# sensors.net
KiCad netlist of a schematic drawn in Altium Designer
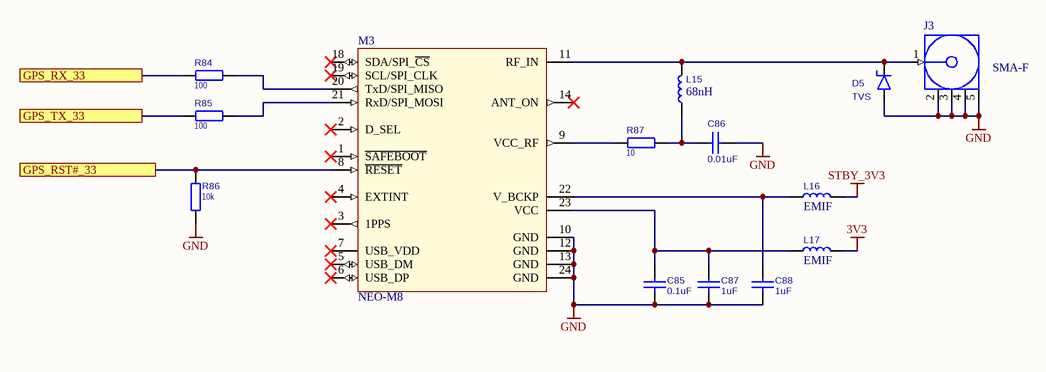
[diagram p0: sensors.SchDoc]

(export (version "E")
  (design (tool "Eeschema 10.0.6"))
  (components
    (comp (ref "C85")
      (value "0.1uF")
      (footprint "Capacitors:C0603")
      (description "CAP_NPOL")
      (fields (field (name "Comment") "C1608X7R1H104K080AA"))
      (libsource (lib "capacitors") (part "CAP_NPOL"))
    )
    (comp (ref "C86")
      (value "0.01uF")
      (footprint "Capacitors:C0603")
      (description "CAP_NPOL")
      (fields (field (name "Comment") "CL10B103KB8NNNC"))
      (libsource (lib "capacitors") (part "CAP_NPOL"))
    )
    (comp (ref "C87")
      (value "1uF")
      (footprint "Capacitors:C0603")
      (description "CAP_NPOL")
      (fields (field (name "Comment") "GRM188R61H105KAALD"))
      (libsource (lib "capacitors") (part "CAP_NPOL"))
    )
    (comp (ref "C88")
      (value "1uF")
      (footprint "Capacitors:C0603")
      (description "CAP_NPOL")
      (fields (field (name "Comment") "GRM188R61H105KAALD"))
      (libsource (lib "capacitors") (part "CAP_NPOL"))
    )
    (comp (ref "D5")
      (value "TVS")
      (footprint "SOD-323")
      (description "TVS Diode")
      (fields (field (name "Comment") "CDSOD323-T05LC"))
      (libsource (lib "diodes") (part "ZENNER_1"))
    )
    (comp (ref "J3")
      (value "SMA-F")
      (footprint "MCX5.08-H5")
      (fields
        (field (name "Comment") "CON SMA-F S-037-TGG R/A PCB")
        (field (name "PUBLISHER") "Altium Limited")
      )
      (libsource (lib "Miscellaneous Connectors") (part "COAX-F"))
    )
    (comp (ref "L15")
      (value "68nH")
      (footprint "IND0603")
      (description "IND_WO_IRON")
      (fields (field (name "Comment") "CLH1608T-68NJ-S"))
      (libsource (lib "inductors") (part "IND_WO_IRON"))
    )
    (comp (ref "L16")
      (value "EMIF")
      (footprint "IND0603")
      (description "IND_WO_IRON")
      (fields (field (name "Comment") "BLM18AG102SN1D"))
      (libsource (lib "inductors") (part "IND_WO_IRON"))
    )
    (comp (ref "L17")
      (value "EMIF")
      (footprint "IND0805")
      (description "IND_WO_IRON")
      (fields (field (name "Comment") "BLM21PG221SN1D"))
      (libsource (lib "") (part "IND_WO_IRON_1"))
    )
    (comp (ref "M3")
      (value "NEO-M8")
      (footprint "NEO-M8N")
      (description "NEO-M8 concurrent GNSS modules")
      (libsource (lib "NEO-M8") (part "NEO-M8"))
    )
    (comp (ref "R84")
      (value "100")
      (footprint "R0603")
      (description "RES")
      (libsource (lib "resistors") (part "RESISTOR"))
    )
    (comp (ref "R85")
      (value "100")
      (footprint "R0603")
      (description "RES")
      (libsource (lib "resistors") (part "RESISTOR"))
    )
    (comp (ref "R86")
      (value "10k")
      (footprint "R0603")
      (description "RES")
      (libsource (lib "resistors") (part "RESISTOR"))
    )
    (comp (ref "R87")
      (value "10")
      (footprint "R0603")
      (description "RES")
      (libsource (lib "resistors") (part "RESISTOR"))
    )
  )
  (nets
    (net (code "1") (name "/GPS_RST#_33") (class "Default")
      (node (ref "M3") (pin "8") (pinfunction "~{RESET}_8") (pintype "input"))
      (node (ref "R86") (pin "1") (pinfunction "1_1") (pintype "passive"))
    )
    (net (code "2") (name "/GPS_RX_33") (class "Default")
      (node (ref "R84") (pin "1") (pinfunction "1_1") (pintype "passive"))
    )
    (net (code "3") (name "/GPS_TX_33") (class "Default")
      (node (ref "R85") (pin "1") (pinfunction "1_1") (pintype "passive"))
    )
    (net (code "4") (name "3V3") (class "Default") (node (ref "L17") (pin "1") (pintype "passive")))
    (net (code "5") (name "GND") (class "Default")
      (node (ref "C85") (pin "2") (pinfunction "2_2") (pintype "passive"))
      (node (ref "C86") (pin "1") (pinfunction "1_1") (pintype "passive"))
      (node (ref "C87") (pin "1") (pinfunction "1_1") (pintype "passive"))
      (node (ref "C88") (pin "1") (pinfunction "1_1") (pintype "passive"))
      (node (ref "D5") (pin "1") (pinfunction "A_1") (pintype "passive"))
      (node (ref "J3") (pin "2") (pinfunction "GND_2") (pintype "power_in"))
      (node (ref "J3") (pin "3") (pinfunction "GND_3") (pintype "power_in"))
      (node (ref "J3") (pin "4") (pinfunction "GND_4") (pintype "power_in"))
      (node (ref "J3") (pin "5") (pinfunction "GND_5") (pintype "power_in"))
      (node (ref "M3") (pin "10") (pinfunction "GND_10") (pintype "power_in"))
      (node (ref "M3") (pin "12") (pinfunction "GND_12") (pintype "power_in"))
      (node (ref "M3") (pin "13") (pinfunction "GND_13") (pintype "power_in"))
      (node (ref "M3") (pin "24") (pinfunction "GND_24") (pintype "power_in"))
      (node (ref "R86") (pin "2") (pinfunction "2_2") (pintype "passive"))
    )
    (net (code "6") (name "Net-(C86-Pad2)") (class "Default")
      (node (ref "C86") (pin "2") (pinfunction "2_2") (pintype "passive"))
      (node (ref "L15") (pin "1") (pintype "passive"))
      (node (ref "R87") (pin "2") (pinfunction "2_2") (pintype "passive"))
    )
    (net (code "7") (name "Net-(D5-K)") (class "Default")
      (node (ref "D5") (pin "2") (pinfunction "K_2") (pintype "passive"))
      (node (ref "J3") (pin "1") (pinfunction "Signal_1") (pintype "input"))
      (node (ref "L15") (pin "2") (pintype "passive"))
      (node (ref "M3") (pin "11") (pinfunction "RF_IN_11") (pintype "passive"))
    )
    (net (code "8") (name "Net-(M3-RxD{slash}SPI_MOSI)") (class "Default")
      (node (ref "M3") (pin "21") (pinfunction "RxD/SPI_MOSI_21") (pintype "input"))
      (node (ref "R85") (pin "2") (pinfunction "2_2") (pintype "passive"))
    )
    (net (code "9") (name "Net-(M3-TxD{slash}SPI_MISO)") (class "Default")
      (node (ref "M3") (pin "20") (pinfunction "TxD/SPI_MISO_20") (pintype "output"))
      (node (ref "R84") (pin "2") (pinfunction "2_2") (pintype "passive"))
    )
    (net (code "10") (name "Net-(M3-VCC)") (class "Default")
      (node (ref "C85") (pin "1") (pinfunction "1_1") (pintype "passive"))
      (node (ref "C87") (pin "2") (pinfunction "2_2") (pintype "passive"))
      (node (ref "L17") (pin "2") (pintype "passive"))
      (node (ref "M3") (pin "23") (pinfunction "VCC_23") (pintype "power_in"))
    )
    (net (code "11") (name "Net-(M3-VCC_RF)") (class "Default")
      (node (ref "M3") (pin "9") (pinfunction "VCC_RF_9") (pintype "output"))
      (node (ref "R87") (pin "1") (pinfunction "1_1") (pintype "passive"))
    )
    (net (code "12") (name "Net-(M3-V_BCKP)") (class "Default")
      (node (ref "C88") (pin "2") (pinfunction "2_2") (pintype "passive"))
      (node (ref "L16") (pin "1") (pintype "passive"))
      (node (ref "M3") (pin "22") (pinfunction "V_BCKP_22") (pintype "power_in"))
    )
    (net (code "13") (name "STBY_3V3") (class "Default") (node (ref "L16") (pin "2") (pintype "passive")))
    (net (code "14") (name "unconnected-(M3-1PPS-Pad3)") (class "Default")
      (node (ref "M3") (pin "3") (pinfunction "1PPS_3") (pintype "output+no_connect"))
    )
    (net (code "15") (name "unconnected-(M3-ANT_ON-Pad14)") (class "Default")
      (node (ref "M3") (pin "14") (pinfunction "ANT_ON_14") (pintype "output+no_connect"))
    )
    (net (code "16") (name "unconnected-(M3-D_SEL-Pad2)") (class "Default")
      (node (ref "M3") (pin "2") (pinfunction "D_SEL_2") (pintype "input+no_connect"))
    )
    (net (code "17") (name "unconnected-(M3-EXTINT-Pad4)") (class "Default")
      (node (ref "M3") (pin "4") (pinfunction "EXTINT_4") (pintype "input+no_connect"))
    )
    (net (code "18") (name "unconnected-(M3-SCL{slash}SPI_CLK-Pad19)") (class "Default")
      (node (ref "M3") (pin "19") (pinfunction "SCL/SPI_CLK_19") (pintype "bidirectional+no_connect"))
    )
    (net (code "19") (name "unconnected-(M3-SDA{slash}SPI_~{CS}-Pad18)") (class "Default")
      (node (ref "M3") (pin "18") (pinfunction "SDA/SPI_~{CS}_18") (pintype "bidirectional+no_connect"))
    )
    (net (code "20") (name "unconnected-(M3-USB_DM-Pad5)") (class "Default")
      (node (ref "M3") (pin "5") (pinfunction "USB_DM_5") (pintype "bidirectional+no_connect"))
    )
    (net (code "21") (name "unconnected-(M3-USB_DP-Pad6)") (class "Default")
      (node (ref "M3") (pin "6") (pinfunction "USB_DP_6") (pintype "bidirectional+no_connect"))
    )
    (net (code "22") (name "unconnected-(M3-USB_VDD-Pad7)") (class "Default")
      (node (ref "M3") (pin "7") (pinfunction "USB_VDD_7") (pintype "power_in+no_connect"))
    )
    (net (code "23") (name "unconnected-(M3-~{SAFEBOOT}-Pad1)") (class "Default")
      (node (ref "M3") (pin "1") (pinfunction "~{SAFEBOOT}_1") (pintype "input+no_connect"))
    )
  )
)
